# PRESS.net
KiCad netlist of a schematic drawn in Altium Designer
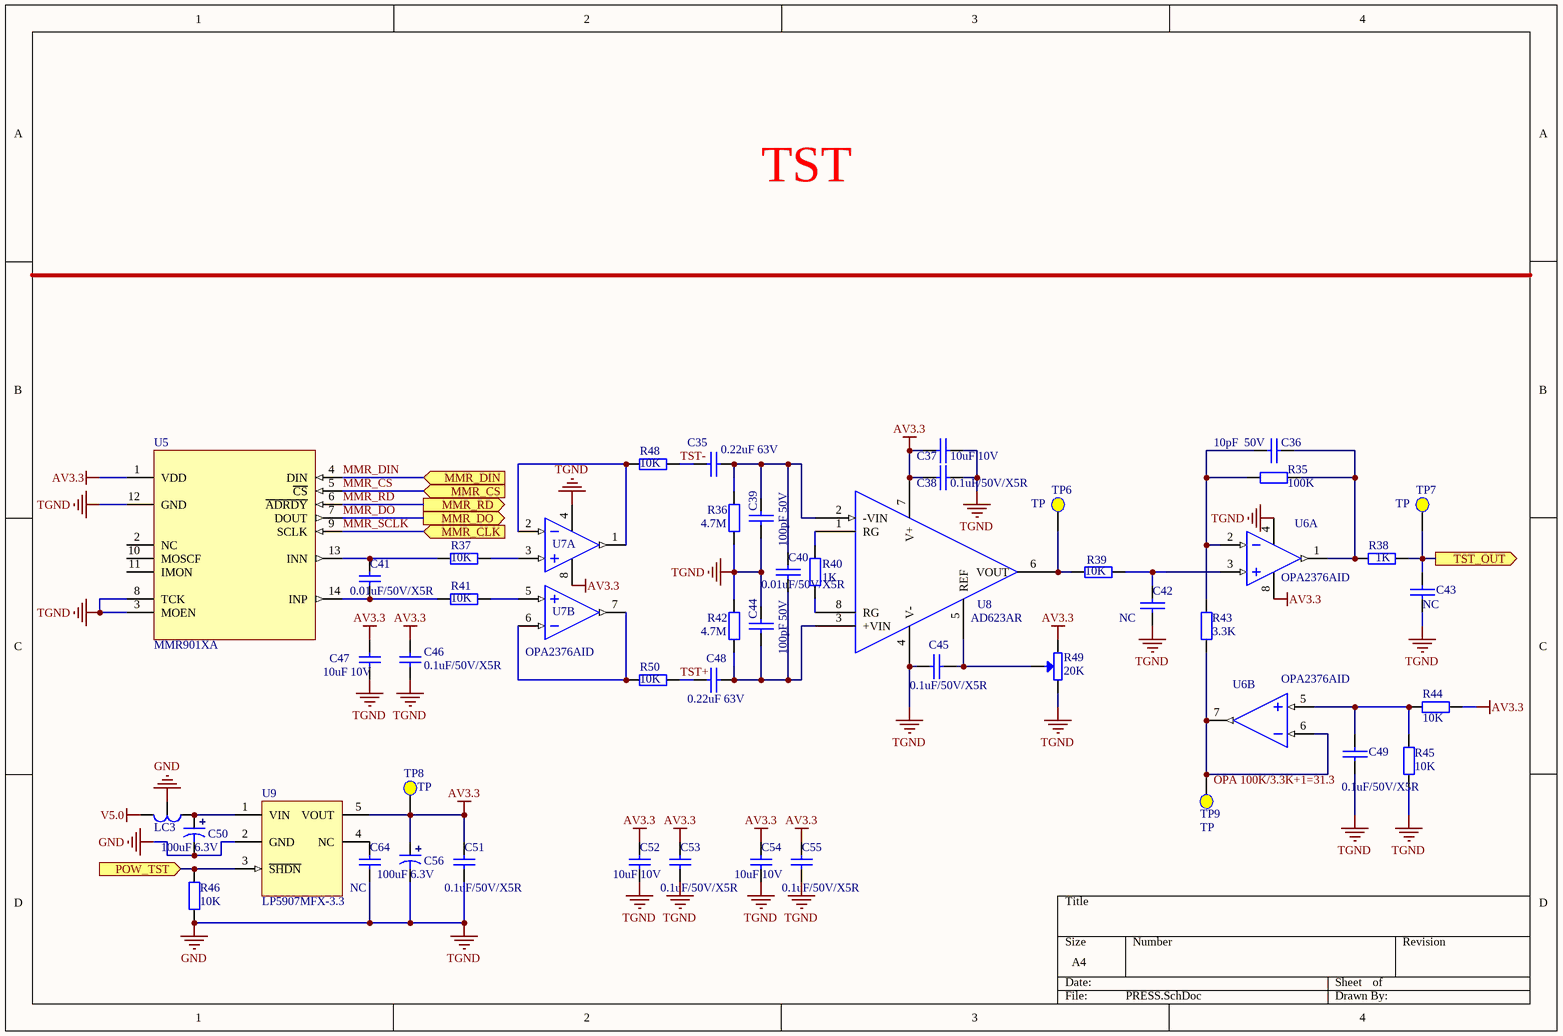
[diagram p0: PRESS.SchDoc]

(export (version "E")
  (design (tool "Eeschema 10.0.6"))
  (components
    (comp (ref "C35")
      (value "0.22uF 63V")
      (footprint "CAP-7.5*5.08")
      (description "CBB电容")
      (libsource (lib "*") (part "CAP"))
    )
    (comp (ref "C36")
      (value "10pF  50V")
      (footprint "SMD-0603C")
      (description "贴片电容 5%")
      (libsource (lib "*") (part "CAP"))
    )
    (comp (ref "C37")
      (value "10uF 10V")
      (footprint "SMD-0603C")
      (description "贴片电容 20%")
      (libsource (lib "*") (part "CAP"))
    )
    (comp (ref "C38")
      (value "0.1uF/50V/X5R")
      (footprint "SMD-0603C")
      (description "贴片电容 5%")
      (libsource (lib "*") (part "CAP"))
    )
    (comp (ref "C39")
      (value "100pF 50V")
      (footprint "SMD-0603C")
      (description "贴片电容 5%")
      (libsource (lib "*") (part "CAP"))
    )
    (comp (ref "C40")
      (value "0.01uF/50V/X5R")
      (footprint "SMD-0603C")
      (description "贴片电容 5%")
      (libsource (lib "*") (part "CAP"))
    )
    (comp (ref "C41")
      (value "0.01uF/50V/X5R")
      (footprint "SMD-0603C")
      (description "贴片电容 10%")
      (libsource (lib "XiaoyI") (part "CAP4"))
    )
    (comp (ref "C42")
      (value "NC")
      (footprint "SMD-0603C")
      (description "贴片电容 5%")
      (libsource (lib "*") (part "CAP"))
    )
    (comp (ref "C43")
      (value "NC")
      (footprint "SMD-0603C")
      (description "贴片电容 5%")
      (libsource (lib "*") (part "CAP"))
    )
    (comp (ref "C44")
      (value "100pF 50V")
      (footprint "SMD-0603C")
      (description "贴片电容 5%")
      (libsource (lib "*") (part "CAP"))
    )
    (comp (ref "C45")
      (value "0.1uF/50V/X5R")
      (footprint "SMD-0603C")
      (description "贴片电容 5%")
      (libsource (lib "*") (part "CAP"))
    )
    (comp (ref "C46")
      (value "0.1uF/50V/X5R")
      (footprint "SMD-0603C")
      (description "贴片电容 10%")
      (libsource (lib "XiaoyI") (part "CAP4"))
    )
    (comp (ref "C47")
      (value "10uF 10V")
      (footprint "SMD-0603C")
      (description "贴片电容 20%")
      (libsource (lib "XiaoyI") (part "CAP4"))
    )
    (comp (ref "C48")
      (value "0.22uF 63V")
      (footprint "CAP-7.5*5.08")
      (description "CBB电容")
      (libsource (lib "*") (part "CAP"))
    )
    (comp (ref "C49")
      (value "0.1uF/50V/X5R")
      (footprint "SMD-0603C")
      (description "贴片电容 5%")
      (libsource (lib "*") (part "CAP"))
    )
    (comp (ref "C50")
      (value "100uF 6.3V")
      (footprint "SMD-3528-B")
      (description "钽电容")
      (libsource (lib "XiaoyI") (part "CAP2"))
    )
    (comp (ref "C51")
      (value "0.1uF/50V/X5R")
      (footprint "SMD-0603C")
      (description "贴片电容 10%")
      (libsource (lib "XiaoyI") (part "CAP4"))
    )
    (comp (ref "C52")
      (value "10uF 10V")
      (footprint "SMD-0603C")
      (description "贴片电容 20%")
      (libsource (lib "XiaoyI") (part "CAP4"))
    )
    (comp (ref "C53")
      (value "0.1uF/50V/X5R")
      (footprint "SMD-0603C")
      (description "贴片电容 10%")
      (libsource (lib "XiaoyI") (part "CAP4"))
    )
    (comp (ref "C54")
      (value "10uF 10V")
      (footprint "SMD-0603C")
      (description "贴片电容 20%")
      (libsource (lib "XiaoyI") (part "CAP4"))
    )
    (comp (ref "C55")
      (value "0.1uF/50V/X5R")
      (footprint "SMD-0603C")
      (description "贴片电容 10%")
      (libsource (lib "XiaoyI") (part "CAP4"))
    )
    (comp (ref "C56")
      (value "100uF 6.3V")
      (footprint "SMD-3528-B")
      (description "钽电容")
      (libsource (lib "XiaoyI") (part "CAP2"))
    )
    (comp (ref "C64")
      (value "NC")
      (footprint "SMD-0603C")
      (description "贴片电容 10%")
      (libsource (lib "XiaoyI") (part "CAP4"))
    )
    (comp (ref "LC3")
      (value "NFM18PC104R1C3")
      (footprint "NFM21P-0805")
      (description "LC滤波器")
      (libsource (lib "XiaoyI") (part "SMD-EMIFIL-0603"))
    )
    (comp (ref "R35")
      (value "100K")
      (footprint "SMD-0603")
      (description "贴片电阻 1%")
      (libsource (lib "") (part "RES0_1"))
    )
    (comp (ref "R36")
      (value "4.7M")
      (footprint "SMD-0603")
      (description "贴片电阻 1%")
      (libsource (lib "") (part "RES0_2"))
    )
    (comp (ref "R37")
      (value "10K")
      (footprint "SMD-0603")
      (description "贴片电阻 1%")
      (libsource (lib "") (part "RES0_3"))
    )
    (comp (ref "R38")
      (value "1K")
      (footprint "SMD-0603")
      (description "贴片电阻 1%")
      (libsource (lib "") (part "RES0_1"))
    )
    (comp (ref "R39")
      (value "10K")
      (footprint "SMD-0603")
      (description "贴片电阻 1%")
      (libsource (lib "") (part "RES0_1"))
    )
    (comp (ref "R40")
      (value "1K")
      (footprint "SMD-0603")
      (description "贴片电阻 1%")
      (libsource (lib "") (part "RES0_2"))
    )
    (comp (ref "R41")
      (value "10K")
      (footprint "SMD-0603")
      (description "贴片电阻 1%")
      (libsource (lib "") (part "RES0_3"))
    )
    (comp (ref "R42")
      (value "4.7M")
      (footprint "SMD-0603")
      (description "贴片电阻 1%")
      (libsource (lib "") (part "RES0_2"))
    )
    (comp (ref "R43")
      (value "3.3K")
      (footprint "SMD-0603")
      (description "贴片电阻 1%")
      (libsource (lib "ABB") (part "RES0"))
    )
    (comp (ref "R44")
      (value "10K")
      (footprint "SMD-0603")
      (description "贴片电阻 1% 低温票电阻")
      (libsource (lib "") (part "RES0_3"))
    )
    (comp (ref "R45")
      (value "10K")
      (footprint "SMD-0603")
      (description "贴片电阻 1% 低温票电阻")
      (libsource (lib "ABB") (part "RES0"))
    )
    (comp (ref "R46")
      (value "10K")
      (footprint "SMD-0603")
      (description "贴片电阻 1%")
      (libsource (lib "") (part "RES0_2"))
    )
    (comp (ref "R48")
      (value "10K")
      (footprint "SMD-0603")
      (description "贴片电阻 1%")
      (libsource (lib "") (part "RES0_3"))
    )
    (comp (ref "R49")
      (value "20K")
      (footprint "VR-05")
      (description "可调电阻")
      (libsource (lib "ABB") (part "RES4"))
    )
    (comp (ref "R50")
      (value "10K")
      (footprint "SMD-0603")
      (description "贴片电阻 1%")
      (libsource (lib "") (part "RES0_3"))
    )
    (comp (ref "TP6") (value "TP") (footprint "TP") (libsource (lib "ABB") (part "TP_POINT")))
    (comp (ref "TP7") (value "TP") (footprint "TP") (libsource (lib "ABB") (part "TP_POINT")))
    (comp (ref "TP8") (value "TP") (footprint "TP") (libsource (lib "ABB") (part "TP_POINT")))
    (comp (ref "TP9") (value "TP") (footprint "TP") (libsource (lib "ABB") (part "TP_POINT")))
    (comp (ref "U5")
      (value "MMR901XA")
      (footprint "MMR901XA")
      (description "压力传感器")
      (libsource (lib "XiaoyI") (part "MMR901"))
    )
    (comp (ref "U6")
      (value "OPA2376AID")
      (footprint "SOIC-8")
      (description "运放")
      (libsource (lib "XiaoyI") (part "LM358"))
    )
    (comp (ref "U7")
      (value "OPA2376AID")
      (footprint "SOIC-8")
      (description "高精度运放")
      (libsource (lib "XiaoyI") (part "LM358"))
    )
    (comp (ref "U8")
      (value "AD623AR")
      (footprint "SOIC-8")
      (description "仪表运放")
      (libsource (lib "*") (part "Component_1"))
    )
    (comp (ref "U9")
      (value "LP5907MFX-3.3")
      (footprint "SOT23-5")
      (description "LDO")
      (libsource (lib "SYELE") (part "MCP1802"))
    )
  )
  (nets
    (net (code "1") (name "/MMR_CS") (class "Default")
      (node (ref "U5") (pin "5") (pinfunction "~{CS}_5") (pintype "input"))
    )
    (net (code "2") (name "/MMR_DIN") (class "Default")
      (node (ref "U5") (pin "4") (pinfunction "DIN_4") (pintype "input"))
    )
    (net (code "3") (name "/MMR_DO") (class "Default")
      (node (ref "U5") (pin "7") (pinfunction "DOUT_7") (pintype "output"))
    )
    (net (code "4") (name "/MMR_RD") (class "Default")
      (node (ref "U5") (pin "6") (pinfunction "~{ADRDY}_6") (pintype "input"))
    )
    (net (code "5") (name "/MMR_SCLK") (class "Default")
      (node (ref "U5") (pin "9") (pinfunction "SCLK_9") (pintype "input"))
    )
    (net (code "6") (name "/POW_TST") (class "Default")
      (node (ref "R46") (pin "1") (pinfunction "1_1") (pintype "passive"))
      (node (ref "U9") (pin "3") (pinfunction "~{SHDN}_3") (pintype "input"))
    )
    (net (code "7") (name "/TST+") (class "Default")
      (node (ref "C48") (pin "2") (pinfunction "2_2") (pintype "passive"))
      (node (ref "R50") (pin "1") (pinfunction "1_1") (pintype "passive"))
    )
    (net (code "8") (name "/TST-") (class "Default")
      (node (ref "C35") (pin "1") (pinfunction "1_1") (pintype "passive"))
      (node (ref "R48") (pin "1") (pinfunction "1_1") (pintype "passive"))
    )
    (net (code "9") (name "/TST_OUT") (class "Default")
      (node (ref "C43") (pin "1") (pinfunction "1_1") (pintype "passive"))
      (node (ref "R38") (pin "2") (pinfunction "2_2") (pintype "passive"))
      (node (ref "TP7") (pin "1") (pinfunction "TP_1") (pintype "power_in"))
    )
    (net (code "10") (name "AV3.3") (class "Default")
      (node (ref "C37") (pin "2") (pinfunction "2_2") (pintype "passive"))
      (node (ref "C38") (pin "2") (pinfunction "2_2") (pintype "passive"))
      (node (ref "C46") (pin "2") (pinfunction "2_2") (pintype "passive"))
      (node (ref "C47") (pin "2") (pinfunction "2_2") (pintype "passive"))
      (node (ref "C51") (pin "2") (pinfunction "2_2") (pintype "passive"))
      (node (ref "C52") (pin "2") (pinfunction "2_2") (pintype "passive"))
      (node (ref "C53") (pin "2") (pinfunction "2_2") (pintype "passive"))
      (node (ref "C54") (pin "2") (pinfunction "2_2") (pintype "passive"))
      (node (ref "C55") (pin "2") (pinfunction "2_2") (pintype "passive"))
      (node (ref "C56") (pin "1") (pinfunction "1_1") (pintype "passive"))
      (node (ref "R44") (pin "1") (pinfunction "1_1") (pintype "passive"))
      (node (ref "R49") (pin "3") (pinfunction "3_3") (pintype "passive"))
      (node (ref "TP8") (pin "1") (pinfunction "TP_1") (pintype "power_in"))
      (node (ref "U5") (pin "1") (pinfunction "VDD_1") (pintype "power_in"))
      (node (ref "U6") (pin "8") (pinfunction "V+_8") (pintype "power_in"))
      (node (ref "U7") (pin "8") (pinfunction "V+_8") (pintype "power_in"))
      (node (ref "U8") (pin "7") (pinfunction "V+_7") (pintype "power_in"))
      (node (ref "U9") (pin "5") (pinfunction "VOUT_5") (pintype "power_in"))
    )
    (net (code "11") (name "GND") (class "Default")
      (node (ref "C37") (pin "1") (pinfunction "1_1") (pintype "passive"))
      (node (ref "C38") (pin "1") (pinfunction "1_1") (pintype "passive"))
      (node (ref "C39") (pin "2") (pinfunction "2_2") (pintype "passive"))
      (node (ref "C42") (pin "1") (pinfunction "1_1") (pintype "passive"))
      (node (ref "C43") (pin "2") (pinfunction "2_2") (pintype "passive"))
      (node (ref "C44") (pin "1") (pinfunction "1_1") (pintype "passive"))
      (node (ref "C45") (pin "1") (pinfunction "1_1") (pintype "passive"))
      (node (ref "C46") (pin "1") (pinfunction "1_1") (pintype "passive"))
      (node (ref "C47") (pin "1") (pinfunction "1_1") (pintype "passive"))
      (node (ref "C49") (pin "1") (pinfunction "1_1") (pintype "passive"))
      (node (ref "C50") (pin "2") (pinfunction "2_2") (pintype "passive"))
      (node (ref "C51") (pin "1") (pinfunction "1_1") (pintype "passive"))
      (node (ref "C52") (pin "1") (pinfunction "1_1") (pintype "passive"))
      (node (ref "C53") (pin "1") (pinfunction "1_1") (pintype "passive"))
      (node (ref "C54") (pin "1") (pinfunction "1_1") (pintype "passive"))
      (node (ref "C55") (pin "1") (pinfunction "1_1") (pintype "passive"))
      (node (ref "C56") (pin "2") (pinfunction "2_2") (pintype "passive"))
      (node (ref "C64") (pin "1") (pinfunction "1_1") (pintype "passive"))
      (node (ref "LC3") (pin "2") (pinfunction "2_2") (pintype "passive"))
      (node (ref "R36") (pin "2") (pinfunction "2_2") (pintype "passive"))
      (node (ref "R42") (pin "1") (pinfunction "1_1") (pintype "passive"))
      (node (ref "R45") (pin "1") (pinfunction "1_1") (pintype "passive"))
      (node (ref "R46") (pin "2") (pinfunction "2_2") (pintype "passive"))
      (node (ref "R49") (pin "1") (pinfunction "1_1") (pintype "passive"))
      (node (ref "U5") (pin "12") (pinfunction "GND_12") (pintype "power_in"))
      (node (ref "U5") (pin "3") (pinfunction "MOEN_3") (pintype "passive"))
      (node (ref "U5") (pin "8") (pinfunction "TCK_8") (pintype "passive"))
      (node (ref "U6") (pin "4") (pinfunction "V-_4") (pintype "power_in"))
      (node (ref "U7") (pin "4") (pinfunction "V-_4") (pintype "power_in"))
      (node (ref "U8") (pin "4") (pinfunction "V-_4") (pintype "power_in"))
      (node (ref "U9") (pin "2") (pinfunction "GND_2") (pintype "power_in"))
    )
    (net (code "12") (name "Net-(R40-Pad1)") (class "Default")
      (node (ref "R40") (pin "1") (pinfunction "1_1") (pintype "passive"))
      (node (ref "U8") (pin "1") (pinfunction "RG_1") (pintype "passive"))
    )
    (net (code "13") (name "Net-(R40-Pad2)") (class "Default")
      (node (ref "R40") (pin "2") (pinfunction "2_2") (pintype "passive"))
      (node (ref "U8") (pin "8") (pinfunction "RG_8") (pintype "passive"))
    )
    (net (code "14") (name "Net-(TP6-TP)") (class "Default")
      (node (ref "R39") (pin "1") (pinfunction "1_1") (pintype "passive"))
      (node (ref "TP6") (pin "1") (pinfunction "TP_1") (pintype "power_in"))
      (node (ref "U8") (pin "6") (pinfunction "VOUT_6") (pintype "passive"))
    )
    (net (code "15") (name "Net-(TP9-TP)") (class "Default")
      (node (ref "R43") (pin "1") (pinfunction "1_1") (pintype "passive"))
      (node (ref "TP9") (pin "1") (pinfunction "TP_1") (pintype "power_in"))
      (node (ref "U6") (pin "6") (pinfunction "IN2-_6") (pintype "input"))
      (node (ref "U6") (pin "7") (pinfunction "OUT2_7") (pintype "output"))
    )
    (net (code "16") (name "Net-(U5-INN)") (class "Default")
      (node (ref "C41") (pin "2") (pinfunction "2_2") (pintype "passive"))
      (node (ref "R37") (pin "2") (pinfunction "2_2") (pintype "passive"))
      (node (ref "U5") (pin "13") (pinfunction "INN_13") (pintype "output"))
    )
    (net (code "17") (name "Net-(U5-INP)") (class "Default")
      (node (ref "C41") (pin "1") (pinfunction "1_1") (pintype "passive"))
      (node (ref "R41") (pin "2") (pinfunction "2_2") (pintype "passive"))
      (node (ref "U5") (pin "14") (pinfunction "INP_14") (pintype "output"))
    )
    (net (code "18") (name "Net-(U6A-IN1+)") (class "Default")
      (node (ref "C42") (pin "2") (pinfunction "2_2") (pintype "passive"))
      (node (ref "R39") (pin "2") (pinfunction "2_2") (pintype "passive"))
      (node (ref "U6") (pin "3") (pinfunction "IN1+_3") (pintype "input"))
    )
    (net (code "19") (name "Net-(U6A-IN1-)") (class "Default")
      (node (ref "C36") (pin "1") (pinfunction "1_1") (pintype "passive"))
      (node (ref "R35") (pin "1") (pinfunction "1_1") (pintype "passive"))
      (node (ref "R43") (pin "2") (pinfunction "2_2") (pintype "passive"))
      (node (ref "U6") (pin "2") (pinfunction "IN1-_2") (pintype "input"))
    )
    (net (code "20") (name "Net-(U6A-OUT1)") (class "Default")
      (node (ref "C36") (pin "2") (pinfunction "2_2") (pintype "passive"))
      (node (ref "R35") (pin "2") (pinfunction "2_2") (pintype "passive"))
      (node (ref "R38") (pin "1") (pinfunction "1_1") (pintype "passive"))
      (node (ref "U6") (pin "1") (pinfunction "OUT1_1") (pintype "output"))
    )
    (net (code "21") (name "Net-(U6B-IN2+)") (class "Default")
      (node (ref "C49") (pin "2") (pinfunction "2_2") (pintype "passive"))
      (node (ref "R44") (pin "2") (pinfunction "2_2") (pintype "passive"))
      (node (ref "R45") (pin "2") (pinfunction "2_2") (pintype "passive"))
      (node (ref "U6") (pin "5") (pinfunction "IN2+_5") (pintype "input"))
    )
    (net (code "22") (name "Net-(U7A-IN1+)") (class "Default")
      (node (ref "R37") (pin "1") (pinfunction "1_1") (pintype "passive"))
      (node (ref "U7") (pin "3") (pinfunction "IN1+_3") (pintype "input"))
    )
    (net (code "23") (name "Net-(U7A-IN1-)") (class "Default")
      (node (ref "R48") (pin "2") (pinfunction "2_2") (pintype "passive"))
      (node (ref "U7") (pin "1") (pinfunction "OUT1_1") (pintype "output"))
      (node (ref "U7") (pin "2") (pinfunction "IN1-_2") (pintype "input"))
    )
    (net (code "24") (name "Net-(U7B-IN2+)") (class "Default")
      (node (ref "R41") (pin "1") (pinfunction "1_1") (pintype "passive"))
      (node (ref "U7") (pin "5") (pinfunction "IN2+_5") (pintype "input"))
    )
    (net (code "25") (name "Net-(U7B-IN2-)") (class "Default")
      (node (ref "R50") (pin "2") (pinfunction "2_2") (pintype "passive"))
      (node (ref "U7") (pin "6") (pinfunction "IN2-_6") (pintype "input"))
      (node (ref "U7") (pin "7") (pinfunction "OUT2_7") (pintype "output"))
    )
    (net (code "26") (name "Net-(U8-+VIN)") (class "Default")
      (node (ref "C40") (pin "2") (pinfunction "2_2") (pintype "passive"))
      (node (ref "C44") (pin "2") (pinfunction "2_2") (pintype "passive"))
      (node (ref "C48") (pin "1") (pinfunction "1_1") (pintype "passive"))
      (node (ref "R42") (pin "2") (pinfunction "2_2") (pintype "passive"))
      (node (ref "U8") (pin "3") (pinfunction "+VIN_3") (pintype "passive"))
    )
    (net (code "27") (name "Net-(U8--VIN)") (class "Default")
      (node (ref "C35") (pin "2") (pinfunction "2_2") (pintype "passive"))
      (node (ref "C39") (pin "1") (pinfunction "1_1") (pintype "passive"))
      (node (ref "C40") (pin "1") (pinfunction "1_1") (pintype "passive"))
      (node (ref "R36") (pin "1") (pinfunction "1_1") (pintype "passive"))
      (node (ref "U8") (pin "2") (pinfunction "-VIN_2") (pintype "input"))
    )
    (net (code "28") (name "Net-(U8-REF)") (class "Default")
      (node (ref "C45") (pin "2") (pinfunction "2_2") (pintype "passive"))
      (node (ref "R49") (pin "2") (pinfunction "2_2") (pintype "passive"))
      (node (ref "U8") (pin "5") (pinfunction "REF_5") (pintype "passive"))
    )
    (net (code "29") (name "Net-(U9-NC)") (class "Default")
      (node (ref "C64") (pin "2") (pinfunction "2_2") (pintype "passive"))
      (node (ref "U9") (pin "4") (pinfunction "NC_4") (pintype "passive"))
    )
    (net (code "30") (name "Net-(U9-VIN)") (class "Default")
      (node (ref "C50") (pin "1") (pinfunction "1_1") (pintype "passive"))
      (node (ref "LC3") (pin "1") (pinfunction "1_1") (pintype "passive"))
      (node (ref "U9") (pin "1") (pinfunction "VIN_1") (pintype "power_in"))
    )
    (net (code "31") (name "V5.0") (class "Default")
      (node (ref "LC3") (pin "3") (pinfunction "3_3") (pintype "passive"))
    )
    (net (code "32") (name "unconnected-(U5-IMON-Pad11)") (class "Default")
      (node (ref "U5") (pin "11") (pinfunction "IMON_11") (pintype "passive"))
    )
    (net (code "33") (name "unconnected-(U5-MOSCF-Pad10)") (class "Default")
      (node (ref "U5") (pin "10") (pinfunction "MOSCF_10") (pintype "passive"))
    )
    (net (code "34") (name "unconnected-(U5-NC-Pad2)") (class "Default")
      (node (ref "U5") (pin "2") (pinfunction "NC_2") (pintype "passive"))
    )
  )
)
